# Top_Level_Schematic.net
KiCad netlist of a schematic drawn in Altium Designer
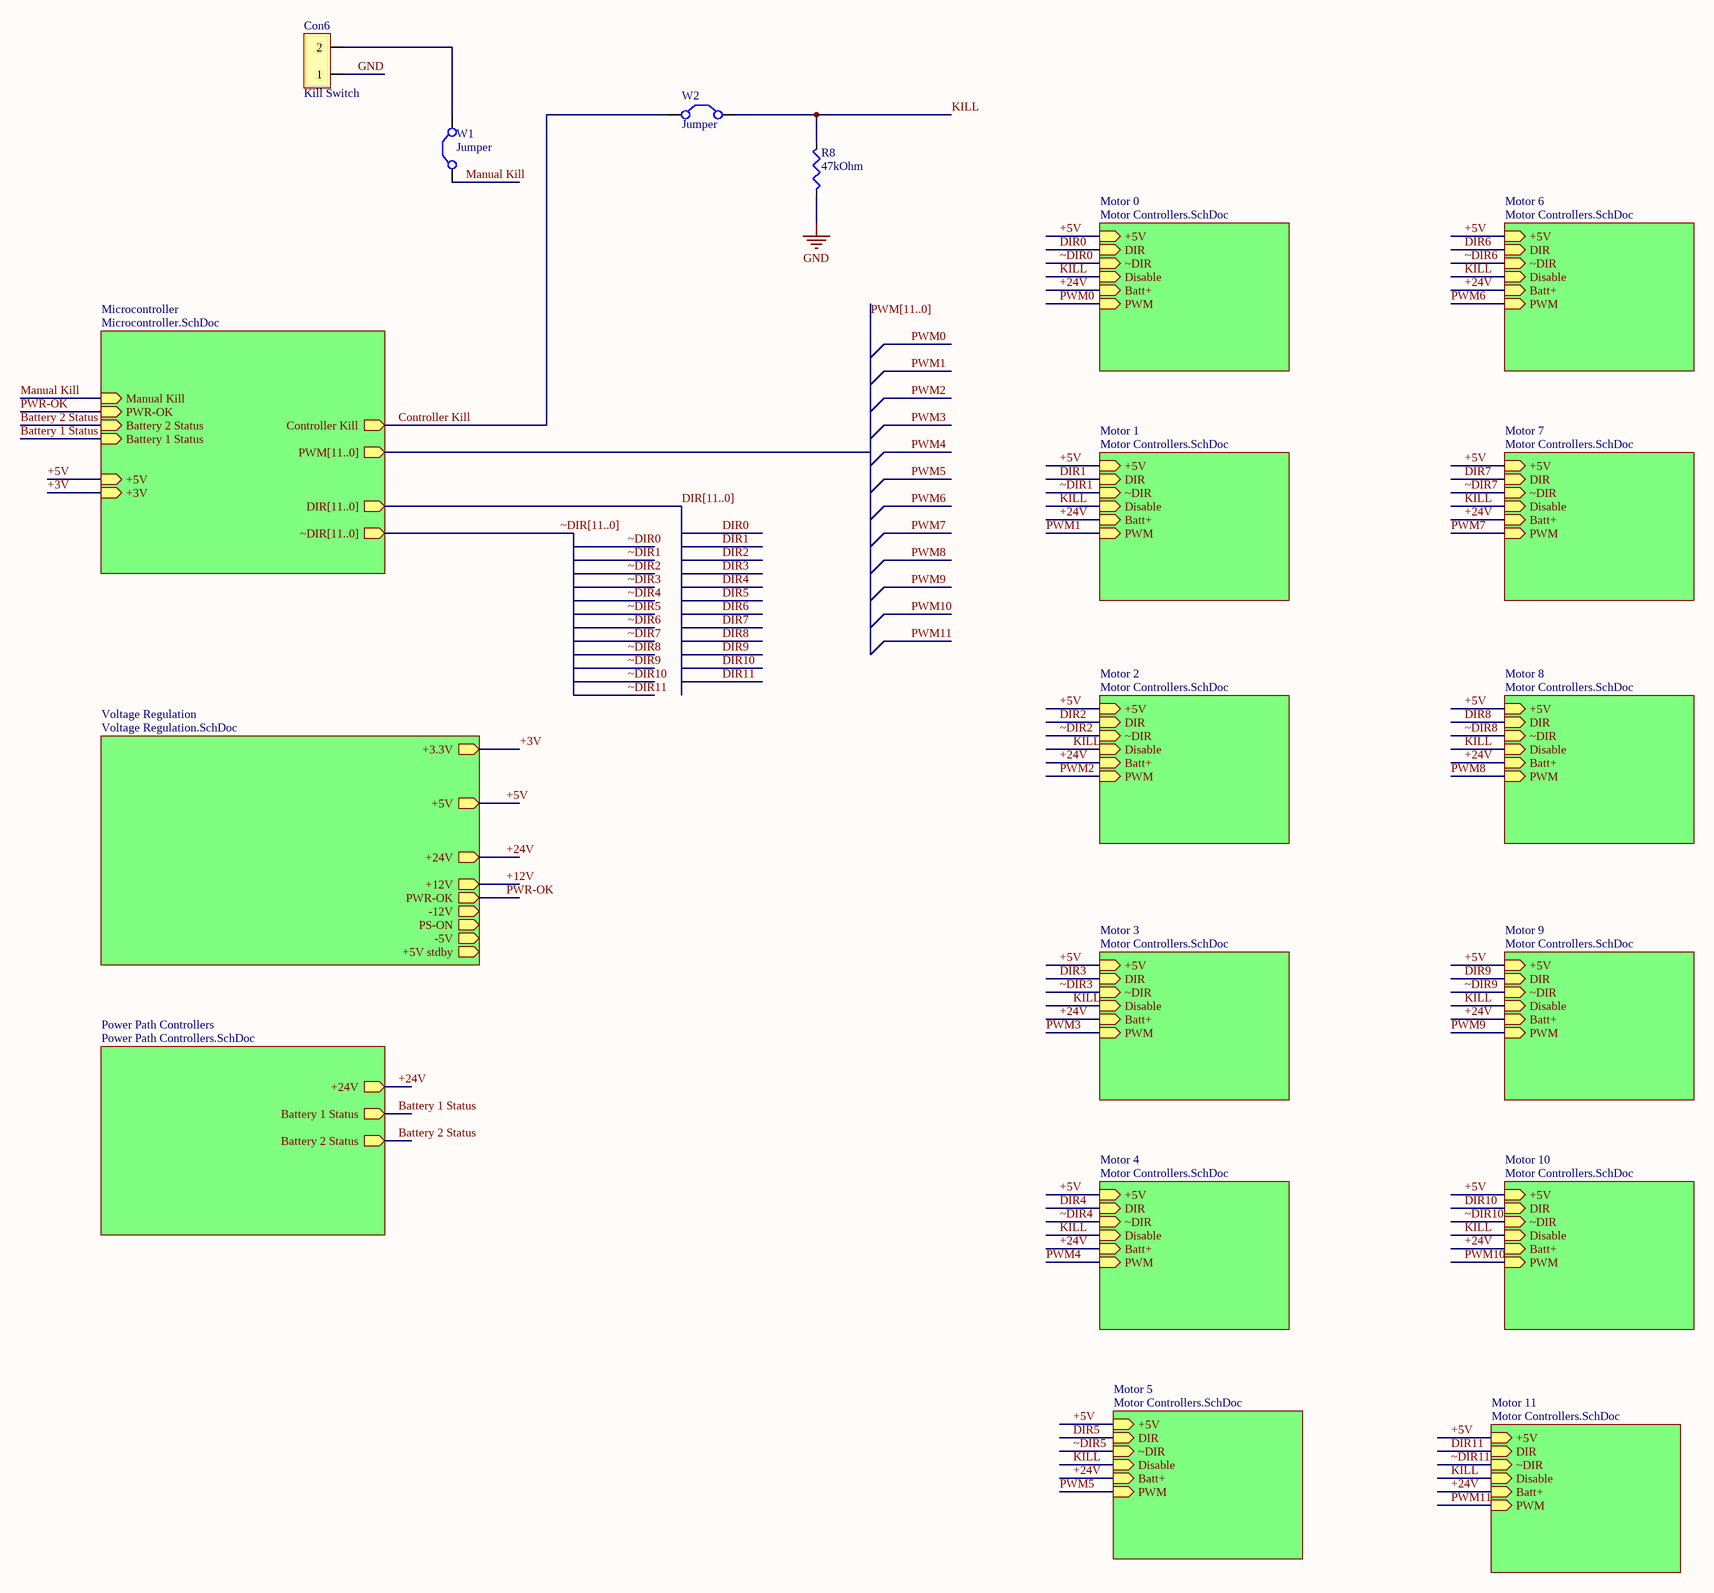
[diagram p0: Top Level Schematic.SchDoc]

(export (version "E")
  (design (tool "Eeschema 10.0.6"))
  (components
    (comp (ref "Con6")
      (value "Kill Switch")
      (footprint "Molex:5569 Mini-Fit Jr 2-Pos Right Angle w/ PCB Mounting Flange")
      (libsource (lib "Molex") (part "5569 Mini-Fit Jr 2-Pos Right Angle"))
    )
    (comp (ref "R8")
      (value "47kOhm")
      (footprint "PassiveComponents:R 1210 (3225) RESISTOR")
      (description "Resistor")
      (libsource (lib "PassiveComponents") (part "Resistor"))
    )
    (comp (ref "W1")
      (value "Jumper")
      (footprint "RAD-0.2")
      (description "Jumper Wire")
      (fields (field (name "PUBLISHER") "Altium Limited"))
      (libsource (lib "Miscellaneous Devices") (part "Jumper"))
    )
    (comp (ref "W2")
      (value "Jumper")
      (footprint "RAD-0.2")
      (description "Jumper Wire")
      (fields (field (name "PUBLISHER") "Altium Limited"))
      (libsource (lib "Miscellaneous Devices") (part "Jumper"))
    )
  )
  (nets
    (net (code "10") (name "/Controller Kill") (class "Default")
      (node (ref "W2") (pin "1") (pinfunction "C1_1") (pintype "passive"))
    )
    (net (code "24") (name "/KILL") (class "Default")
      (node (ref "R8") (pin "2") (pinfunction "2_2") (pintype "passive"))
      (node (ref "W2") (pin "2") (pinfunction "C2_2") (pintype "passive"))
    )
    (net (code "25") (name "/Manual Kill") (class "Default")
      (node (ref "W1") (pin "1") (pinfunction "C1_1") (pintype "passive"))
    )
    (net (code "55") (name "GND") (class "Default")
      (node (ref "Con6") (pin "1") (pinfunction "1_1") (pintype "passive"))
      (node (ref "R8") (pin "1") (pinfunction "1_1") (pintype "passive"))
    )
    (net (code "56") (name "Net-(W1-C2)") (class "Default")
      (node (ref "Con6") (pin "2") (pinfunction "2_2") (pintype "passive"))
      (node (ref "W1") (pin "2") (pinfunction "C2_2") (pintype "passive"))
    )
  )
)
